# iPhone11ProMaxWXCD.net
KiCad netlist of a schematic drawn in Altium Designer
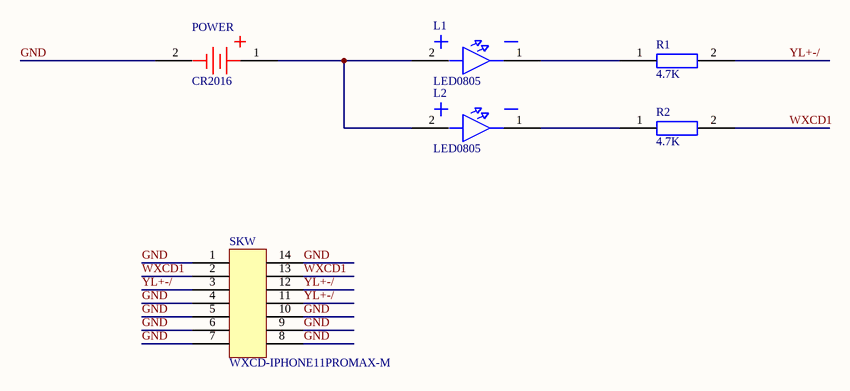
[diagram p0: iPhone11ProMaxWXCD.SchDoc]

(export (version "E")
  (design (tool "Eeschema 10.0.6"))
  (components
    (comp (ref "L1") (value "LED0805") (footprint "LED0805") (libsource (lib "iPhone") (part "LED0805")))
    (comp (ref "L2") (value "LED0805") (footprint "LED0805") (libsource (lib "iPhone") (part "LED0805")))
    (comp (ref "POWER") (value "CR2016") (footprint "CR2016") (libsource (lib "iPhone") (part "CR2016")))
    (comp (ref "R1") (value "4.7K") (footprint "R0805") (libsource (lib "iPhone") (part "R0805")))
    (comp (ref "R2") (value "4.7K") (footprint "R0805") (libsource (lib "iPhone") (part "R0805")))
    (comp (ref "SKW")
      (value "WXCD-IPHONE11PROMAX-M")
      (footprint "IPHONE11PROMAX-WXCD-M")
      (libsource (lib "iPhone") (part "WXCD-IPHONE11PROMAX-M"))
    )
  )
  (nets
    (net (code "1") (name "/GND") (class "Default")
      (node (ref "POWER") (pin "2") (pintype "passive"))
      (node (ref "SKW") (pin "1") (pintype "passive"))
      (node (ref "SKW") (pin "10") (pintype "passive"))
      (node (ref "SKW") (pin "14") (pintype "passive"))
      (node (ref "SKW") (pin "4") (pintype "passive"))
      (node (ref "SKW") (pin "5") (pintype "passive"))
      (node (ref "SKW") (pin "6") (pintype "passive"))
      (node (ref "SKW") (pin "7") (pintype "passive"))
      (node (ref "SKW") (pin "8") (pintype "passive"))
      (node (ref "SKW") (pin "9") (pintype "passive"))
    )
    (net (code "2") (name "/WXCD1") (class "Default")
      (node (ref "R2") (pin "2") (pintype "passive"))
      (node (ref "SKW") (pin "13") (pintype "passive"))
      (node (ref "SKW") (pin "2") (pintype "passive"))
    )
    (net (code "3") (name "/YL+-{slash}") (class "Default")
      (node (ref "R1") (pin "2") (pintype "passive"))
      (node (ref "SKW") (pin "11") (pintype "passive"))
      (node (ref "SKW") (pin "12") (pintype "passive"))
      (node (ref "SKW") (pin "3") (pintype "passive"))
    )
    (net (code "4") (name "Net-(L1-Pad1)") (class "Default")
      (node (ref "L1") (pin "1") (pintype "passive"))
      (node (ref "R1") (pin "1") (pintype "passive"))
    )
    (net (code "5") (name "Net-(L1-Pad2)") (class "Default")
      (node (ref "L1") (pin "2") (pintype "passive"))
      (node (ref "L2") (pin "2") (pintype "passive"))
      (node (ref "POWER") (pin "1") (pintype "passive"))
    )
    (net (code "6") (name "Net-(L2-Pad1)") (class "Default")
      (node (ref "L2") (pin "1") (pintype "passive"))
      (node (ref "R2") (pin "1") (pintype "passive"))
    )
  )
)
